# E72.net
KiCad netlist of a schematic drawn in Altium Designer
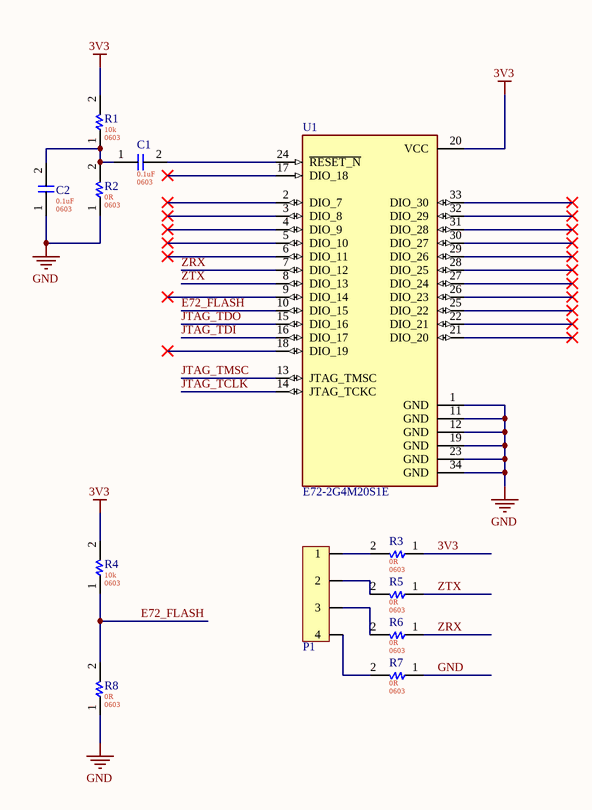
[diagram p0: E72.SchDoc]

(export (version "E")
  (design (tool "Eeschema 10.0.6"))
  (components
    (comp (ref "C1")
      (value "0.1uF")
      (footprint "0603 C")
      (description "CAP CER 0.1uF 50V 10% 0603 SMD")
      (fields (field (name "FP") "0603") (field (name "CREATOR") "MMUOP"))
      (libsource (lib "Capacitor") (part "0603 0.1uF CER"))
    )
    (comp (ref "C2")
      (value "0.1uF")
      (footprint "0603 C")
      (description "CAP CER 0.1uF 50V 10% 0603 SMD")
      (fields (field (name "FP") "0603") (field (name "CREATOR") "MMUOP"))
      (libsource (lib "Capacitor") (part "0603 0.1uF CER"))
    )
    (comp (ref "P1") (value "P4") (footprint "P4 - 2.54mm") (libsource (lib "Kienlib") (part "P4")))
    (comp (ref "R1")
      (value "10k")
      (footprint "RES 0603")
      (description "10k 1% 0603 SMD")
      (fields (field (name "FP") "0603") (field (name "CREATOR") "MMUOP"))
      (libsource (lib "Res") (part "0603 10k 1%"))
    )
    (comp (ref "R2")
      (value "0R")
      (footprint "RES 0603")
      (description "0R 1% 0603 SMD")
      (fields (field (name "FP") "0603") (field (name "Comment") "10k") (field (name "CREATOR") "MMUOP"))
      (libsource (lib "Res") (part "0603 10k 1%"))
    )
    (comp (ref "R3")
      (value "0R")
      (footprint "RES 0603")
      (description "0R 1% 0603 SMD")
      (fields (field (name "FP") "0603") (field (name "Comment") "10k") (field (name "CREATOR") "MMUOP"))
      (libsource (lib "Res") (part "0603 10k 1%"))
    )
    (comp (ref "R4")
      (value "10k")
      (footprint "RES 0603")
      (description "10k 1% 0603 SMD")
      (fields (field (name "FP") "0603") (field (name "CREATOR") "MMUOP"))
      (libsource (lib "Res") (part "0603 10k 1%"))
    )
    (comp (ref "R5")
      (value "0R")
      (footprint "RES 0603")
      (description "0R 1% 0603 SMD")
      (fields (field (name "FP") "0603") (field (name "Comment") "10k") (field (name "CREATOR") "MMUOP"))
      (libsource (lib "Res") (part "0603 10k 1%"))
    )
    (comp (ref "R6")
      (value "0R")
      (footprint "RES 0603")
      (description "0R 1% 0603 SMD")
      (fields (field (name "FP") "0603") (field (name "Comment") "10k") (field (name "CREATOR") "MMUOP"))
      (libsource (lib "Res") (part "0603 10k 1%"))
    )
    (comp (ref "R7")
      (value "0R")
      (footprint "RES 0603")
      (description "0R 1% 0603 SMD")
      (fields (field (name "FP") "0603") (field (name "Comment") "10k") (field (name "CREATOR") "MMUOP"))
      (libsource (lib "Res") (part "0603 10k 1%"))
    )
    (comp (ref "R8")
      (value "0R")
      (footprint "RES 0603")
      (description "0R 1% 0603 SMD")
      (fields (field (name "FP") "0603") (field (name "Comment") "10k") (field (name "CREATOR") "MMUOP"))
      (libsource (lib "Res") (part "0603 10k 1%"))
    )
    (comp (ref "U1")
      (value "E72-2G4M20S1E")
      (footprint "Module_E72")
      (description "CC2652P Multifunctional SoC wireless module")
      (fields (field (name "MF") "EBYTE"))
      (libsource (lib "thuvienthong_Module") (part "E72-2G4M20S1E"))
    )
  )
  (nets
    (net (code "1") (name "/E72_FLASH") (class "Default")
      (node (ref "R4") (pin "1") (pinfunction "1_1") (pintype "passive"))
      (node (ref "R8") (pin "2") (pinfunction "2_2") (pintype "passive"))
      (node (ref "U1") (pin "10") (pinfunction "DIO_15_10") (pintype "bidirectional"))
    )
    (net (code "2") (name "/JTAG_TCLK") (class "Default")
      (node (ref "U1") (pin "14") (pinfunction "JTAG_TCKC_14") (pintype "bidirectional"))
    )
    (net (code "3") (name "/JTAG_TDI") (class "Default")
      (node (ref "U1") (pin "16") (pinfunction "DIO_17_16") (pintype "bidirectional"))
    )
    (net (code "4") (name "/JTAG_TDO") (class "Default")
      (node (ref "U1") (pin "15") (pinfunction "DIO_16_15") (pintype "bidirectional"))
    )
    (net (code "5") (name "/JTAG_TMSC") (class "Default")
      (node (ref "U1") (pin "13") (pinfunction "JTAG_TMSC_13") (pintype "bidirectional"))
    )
    (net (code "6") (name "/ZRX") (class "Default")
      (node (ref "R6") (pin "1") (pinfunction "1_1") (pintype "passive"))
      (node (ref "U1") (pin "7") (pinfunction "DIO_12_7") (pintype "bidirectional"))
    )
    (net (code "7") (name "/ZTX") (class "Default")
      (node (ref "R5") (pin "1") (pinfunction "1_1") (pintype "passive"))
      (node (ref "U1") (pin "8") (pinfunction "DIO_13_8") (pintype "bidirectional"))
    )
    (net (code "8") (name "3V3") (class "Default")
      (node (ref "R1") (pin "2") (pinfunction "2_2") (pintype "passive"))
      (node (ref "R3") (pin "1") (pinfunction "1_1") (pintype "passive"))
      (node (ref "R4") (pin "2") (pinfunction "2_2") (pintype "passive"))
      (node (ref "U1") (pin "20") (pinfunction "VCC_20") (pintype "power_in"))
    )
    (net (code "9") (name "GND") (class "Default")
      (node (ref "C2") (pin "1") (pinfunction "1_1") (pintype "passive"))
      (node (ref "R2") (pin "1") (pinfunction "1_1") (pintype "passive"))
      (node (ref "R7") (pin "1") (pinfunction "1_1") (pintype "passive"))
      (node (ref "R8") (pin "1") (pinfunction "1_1") (pintype "passive"))
      (node (ref "U1") (pin "1") (pinfunction "GND_1") (pintype "power_in"))
      (node (ref "U1") (pin "11") (pinfunction "GND_11") (pintype "power_in"))
      (node (ref "U1") (pin "12") (pinfunction "GND_12") (pintype "power_in"))
      (node (ref "U1") (pin "19") (pinfunction "GND_19") (pintype "power_in"))
      (node (ref "U1") (pin "23") (pinfunction "GND_23") (pintype "power_in"))
      (node (ref "U1") (pin "34") (pinfunction "GND_34") (pintype "power_in"))
    )
    (net (code "10") (name "Net-(C1-Pad1)") (class "Default")
      (node (ref "C1") (pin "1") (pinfunction "1_1") (pintype "passive"))
      (node (ref "C2") (pin "2") (pinfunction "2_2") (pintype "passive"))
      (node (ref "R1") (pin "1") (pinfunction "1_1") (pintype "passive"))
      (node (ref "R2") (pin "2") (pinfunction "2_2") (pintype "passive"))
    )
    (net (code "11") (name "Net-(P1-Pad1)") (class "Default")
      (node (ref "P1") (pin "1") (pinfunction "1_1") (pintype "passive"))
      (node (ref "R3") (pin "2") (pinfunction "2_2") (pintype "passive"))
    )
    (net (code "12") (name "Net-(P1-Pad2)") (class "Default")
      (node (ref "P1") (pin "2") (pinfunction "2_2") (pintype "passive"))
      (node (ref "R5") (pin "2") (pinfunction "2_2") (pintype "passive"))
    )
    (net (code "13") (name "Net-(P1-Pad3)") (class "Default")
      (node (ref "P1") (pin "3") (pinfunction "3_3") (pintype "passive"))
      (node (ref "R6") (pin "2") (pinfunction "2_2") (pintype "passive"))
    )
    (net (code "14") (name "Net-(P1-Pad4)") (class "Default")
      (node (ref "P1") (pin "4") (pinfunction "4_4") (pintype "passive"))
      (node (ref "R7") (pin "2") (pinfunction "2_2") (pintype "passive"))
    )
    (net (code "15") (name "Net-(U1-~{RESET_N})") (class "Default")
      (node (ref "C1") (pin "2") (pinfunction "2_2") (pintype "passive"))
      (node (ref "U1") (pin "24") (pinfunction "~{RESET_N}_24") (pintype "input"))
    )
    (net (code "16") (name "unconnected-(U1-DIO_7-Pad2)") (class "Default")
      (node (ref "U1") (pin "2") (pinfunction "DIO_7_2") (pintype "bidirectional+no_connect"))
    )
    (net (code "17") (name "unconnected-(U1-DIO_8-Pad3)") (class "Default")
      (node (ref "U1") (pin "3") (pinfunction "DIO_8_3") (pintype "bidirectional+no_connect"))
    )
    (net (code "18") (name "unconnected-(U1-DIO_9-Pad4)") (class "Default")
      (node (ref "U1") (pin "4") (pinfunction "DIO_9_4") (pintype "bidirectional+no_connect"))
    )
    (net (code "19") (name "unconnected-(U1-DIO_10-Pad5)") (class "Default")
      (node (ref "U1") (pin "5") (pinfunction "DIO_10_5") (pintype "bidirectional+no_connect"))
    )
    (net (code "20") (name "unconnected-(U1-DIO_11-Pad6)") (class "Default")
      (node (ref "U1") (pin "6") (pinfunction "DIO_11_6") (pintype "bidirectional+no_connect"))
    )
    (net (code "21") (name "unconnected-(U1-DIO_14-Pad9)") (class "Default")
      (node (ref "U1") (pin "9") (pinfunction "DIO_14_9") (pintype "bidirectional+no_connect"))
    )
    (net (code "22") (name "unconnected-(U1-DIO_18-Pad17)") (class "Default")
      (node (ref "U1") (pin "17") (pinfunction "DIO_18_17") (pintype "input+no_connect"))
    )
    (net (code "23") (name "unconnected-(U1-DIO_19-Pad18)") (class "Default")
      (node (ref "U1") (pin "18") (pinfunction "DIO_19_18") (pintype "bidirectional+no_connect"))
    )
    (net (code "24") (name "unconnected-(U1-DIO_20-Pad21)") (class "Default")
      (node (ref "U1") (pin "21") (pinfunction "DIO_20_21") (pintype "bidirectional+no_connect"))
    )
    (net (code "25") (name "unconnected-(U1-DIO_21-Pad22)") (class "Default")
      (node (ref "U1") (pin "22") (pinfunction "DIO_21_22") (pintype "bidirectional+no_connect"))
    )
    (net (code "26") (name "unconnected-(U1-DIO_22-Pad25)") (class "Default")
      (node (ref "U1") (pin "25") (pinfunction "DIO_22_25") (pintype "bidirectional+no_connect"))
    )
    (net (code "27") (name "unconnected-(U1-DIO_23-Pad26)") (class "Default")
      (node (ref "U1") (pin "26") (pinfunction "DIO_23_26") (pintype "bidirectional+no_connect"))
    )
    (net (code "28") (name "unconnected-(U1-DIO_24-Pad27)") (class "Default")
      (node (ref "U1") (pin "27") (pinfunction "DIO_24_27") (pintype "bidirectional+no_connect"))
    )
    (net (code "29") (name "unconnected-(U1-DIO_25-Pad28)") (class "Default")
      (node (ref "U1") (pin "28") (pinfunction "DIO_25_28") (pintype "bidirectional+no_connect"))
    )
    (net (code "30") (name "unconnected-(U1-DIO_26-Pad29)") (class "Default")
      (node (ref "U1") (pin "29") (pinfunction "DIO_26_29") (pintype "bidirectional+no_connect"))
    )
    (net (code "31") (name "unconnected-(U1-DIO_27-Pad30)") (class "Default")
      (node (ref "U1") (pin "30") (pinfunction "DIO_27_30") (pintype "bidirectional+no_connect"))
    )
    (net (code "32") (name "unconnected-(U1-DIO_28-Pad31)") (class "Default")
      (node (ref "U1") (pin "31") (pinfunction "DIO_28_31") (pintype "bidirectional+no_connect"))
    )
    (net (code "33") (name "unconnected-(U1-DIO_29-Pad32)") (class "Default")
      (node (ref "U1") (pin "32") (pinfunction "DIO_29_32") (pintype "bidirectional+no_connect"))
    )
    (net (code "34") (name "unconnected-(U1-DIO_30-Pad33)") (class "Default")
      (node (ref "U1") (pin "33") (pinfunction "DIO_30_33") (pintype "bidirectional+no_connect"))
    )
  )
)
